# DRIVERS_CONNECTORS.net
KiCad netlist of a schematic drawn in Altium Designer
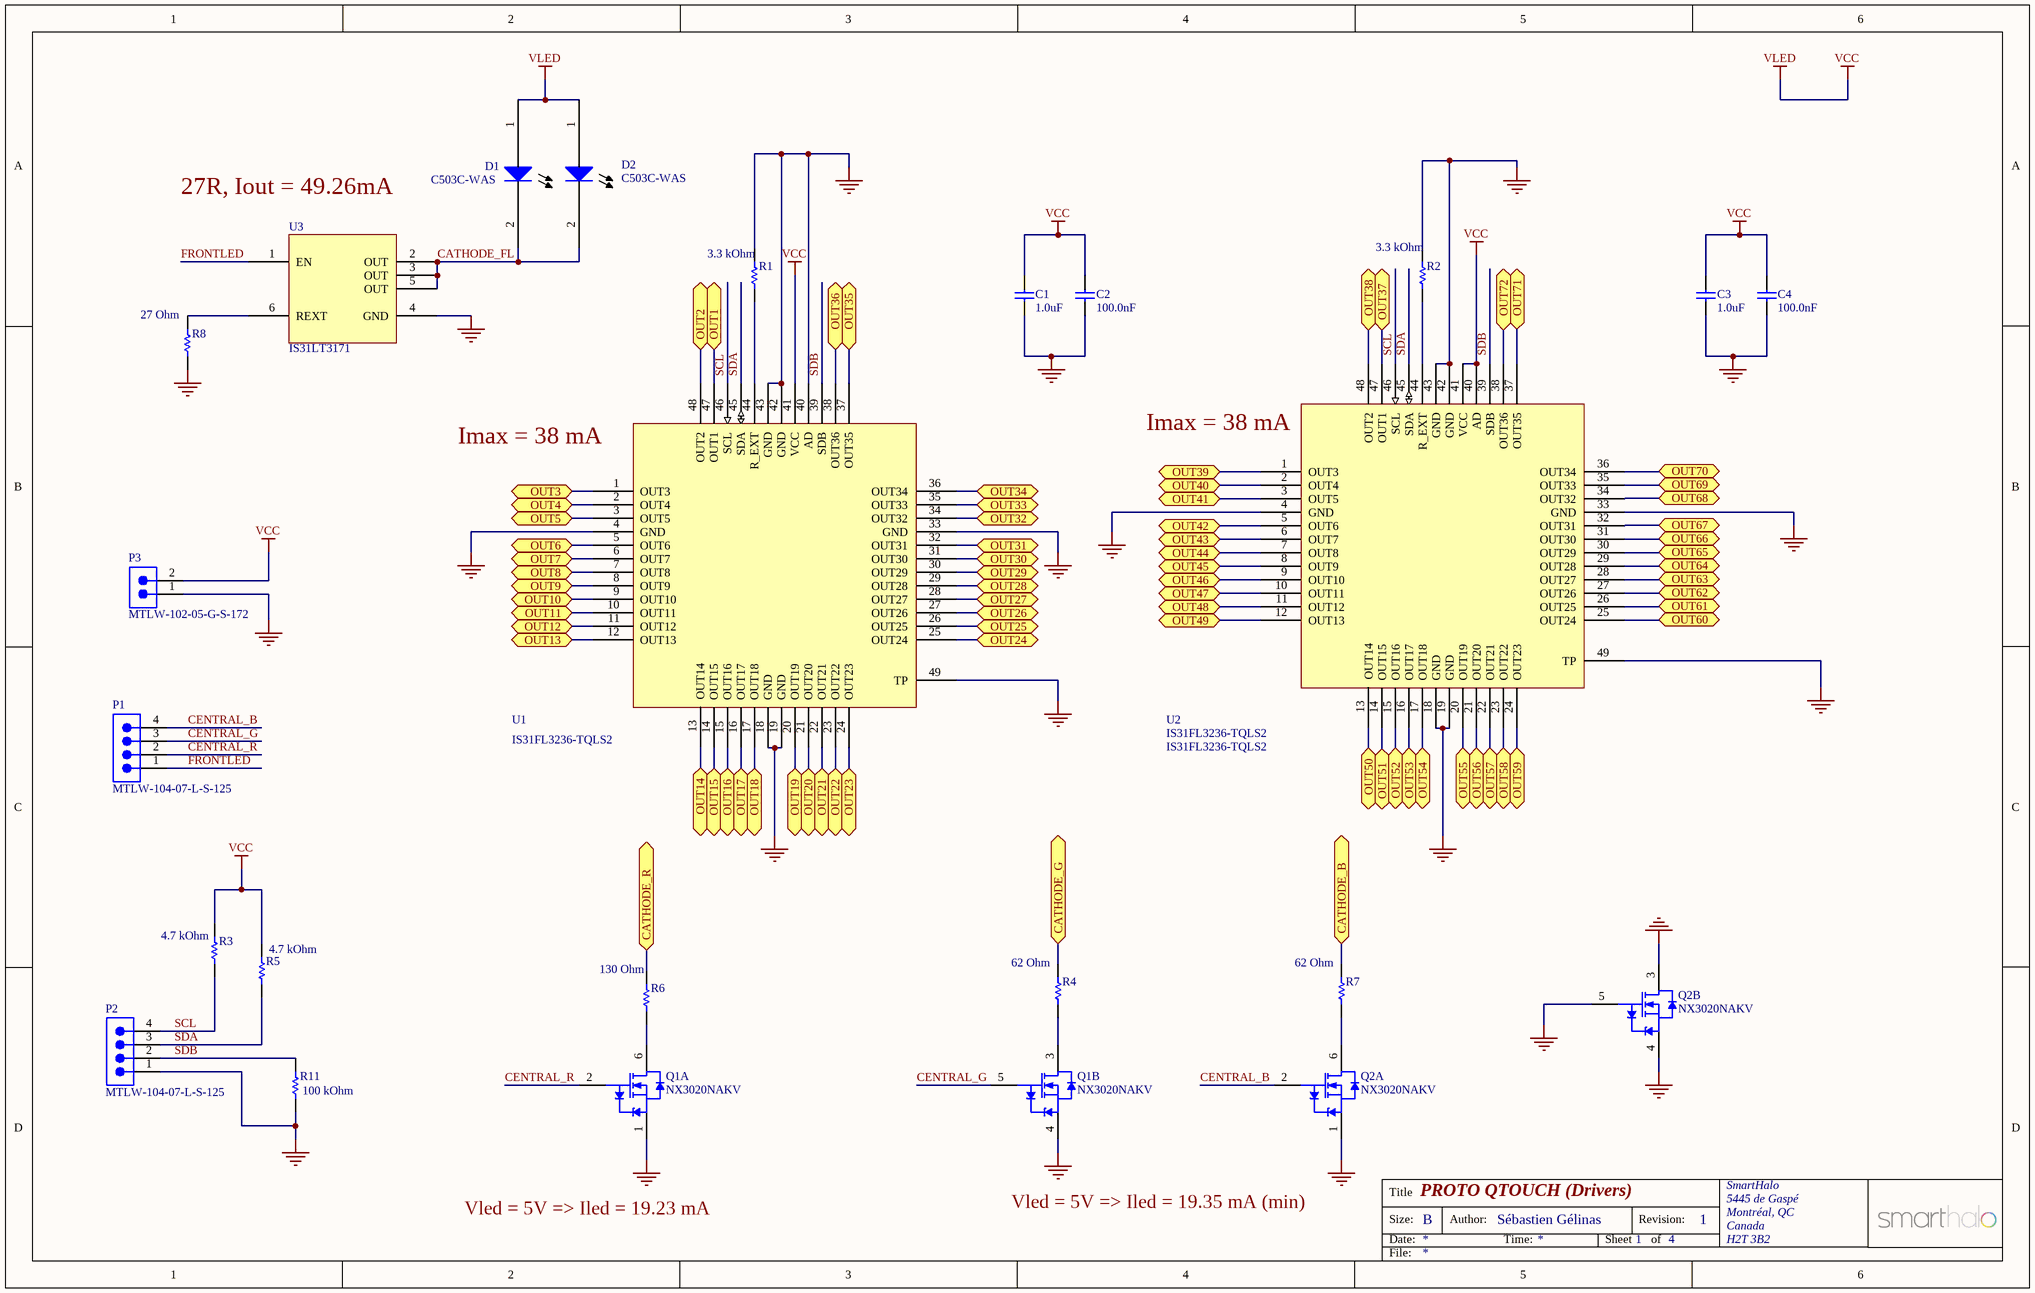
[diagram p0: DRIVERS_CONNECTORS.SchDoc]

(export (version "E")
  (design (tool "Eeschema 10.0.6"))
  (components
    (comp (ref "C1")
      (value "1.0uF")
      (footprint "CAPC0603(1608)100_N")
      (description "Chip Cap 0603 X7R 10%")
      (fields (field (name "PART NUMBER") "C0402-1n0") (field (name "PUBLISHER") "Nordic Semiconductor"))
      (libsource (lib "SmartHalo") (part "CAP0603"))
    )
    (comp (ref "C2")
      (value "100.0nF")
      (footprint "CAPC0603(1608)100_N")
      (description "Chip Cap 0603 X7R 10%")
      (fields (field (name "PART NUMBER") "C0402-1n0") (field (name "PUBLISHER") "Nordic Semiconductor"))
      (libsource (lib "SmartHalo") (part "CAP0603"))
    )
    (comp (ref "C3")
      (value "1.0uF")
      (footprint "CAPC0603(1608)100_N")
      (description "Chip Cap 0603 X7R 10%")
      (fields (field (name "PART NUMBER") "C0402-1n0") (field (name "PUBLISHER") "Nordic Semiconductor"))
      (libsource (lib "SmartHalo") (part "CAP0603"))
    )
    (comp (ref "C4")
      (value "100.0nF")
      (footprint "CAPC0603(1608)100_N")
      (description "Chip Cap 0603 X7R 10%")
      (fields (field (name "PART NUMBER") "C0402-1n0") (field (name "PUBLISHER") "Nordic Semiconductor"))
      (libsource (lib "SmartHalo") (part "CAP0603"))
    )
    (comp (ref "D1")
      (value "C503C-WAS")
      (footprint "FRONTLED_PADS")
      (description "Cree 5mm Round LED C503C-WAS")
      (libsource (lib "SmartHalo") (part "C503C-WAS"))
    )
    (comp (ref "D2")
      (value "C503C-WAS")
      (footprint "FRONTLED_PADS")
      (description "Cree 5mm Round LED C503C-WAS")
      (libsource (lib "SmartHalo") (part "C503C-WAS"))
    )
    (comp (ref "P1")
      (value "MTLW-104-07-L-S-125")
      (footprint "SMTC-MTLW-104-07-X-S-125")
      (fields (field (name "MANUFACTURER") "Samtec"))
      (libsource (lib "SmartHalo") (part "SMTC-MTLW-104-07-X-S-125"))
    )
    (comp (ref "P2")
      (value "MTLW-104-07-L-S-125")
      (footprint "SMTC-MTLW-104-07-X-S-125")
      (fields (field (name "MANUFACTURER") "Samtec"))
      (libsource (lib "SmartHalo") (part "SMTC-MTLW-104-07-X-S-125"))
    )
    (comp (ref "P3")
      (value "MTLW-102-05-G-S-172")
      (footprint "SMTC-MTLW-102-05-X-S-172")
      (fields (field (name "MANUFACTURER") "Samtec"))
      (libsource (lib "SmartHalo") (part "SMTC-MTLW-102-05-X-S-172"))
    )
    (comp (ref "Q1")
      (value "NX3020NAKV")
      (footprint "SOT666")
      (description "30 V, 200 mA dual N-channel Trench MOSFET")
      (fields (field (name "MANUFACTURER") "NXP Semiconductors"))
      (libsource (lib "SmartHalo") (part "NX3020NAKV"))
    )
    (comp (ref "Q2")
      (value "NX3020NAKV")
      (footprint "SOT666")
      (description "30 V, 200 mA dual N-channel Trench MOSFET")
      (fields (field (name "MANUFACTURER") "NXP Semiconductors"))
      (libsource (lib "SmartHalo") (part "NX3020NAKV"))
    )
    (comp (ref "R1")
      (value "3.3 kOhm")
      (footprint "RESC0603(1608)_M")
      (description "3K3 0.1W 5% 0603 (1608 Metric)  SMD")
      (fields (field (name "TOLERANCE") "5 %") (field (name "POWER") "0.1 W"))
      (libsource (lib "SmartHalo") (part "CMP-1012-00090-1"))
    )
    (comp (ref "R2")
      (value "3.3 kOhm")
      (footprint "RESC0603(1608)_M")
      (description "3K3 0.1W 5% 0603 (1608 Metric)  SMD")
      (fields (field (name "TOLERANCE") "5 %") (field (name "POWER") "0.1 W"))
      (libsource (lib "SmartHalo") (part "CMP-1012-00090-1"))
    )
    (comp (ref "R3")
      (value "4.7 kOhm")
      (footprint "RESC0603(1608)_M")
      (description "4K7 0.1W 5% 0603 (1608 Metric)  SMD")
      (fields (field (name "TOLERANCE") "5 %") (field (name "POWER") "0.1 W"))
      (libsource (lib "SmartHalo") (part "CMP-1012-00090-1"))
    )
    (comp (ref "R4")
      (value "62 Ohm")
      (footprint "RESC0603(1608)_M")
      (description "62R 0.1W 5% 0603 (1608 Metric)  SMD")
      (fields (field (name "TOLERANCE") "5 %") (field (name "POWER") "0.1 W"))
      (libsource (lib "SmartHalo") (part "CMP-1012-00090-1"))
    )
    (comp (ref "R5")
      (value "4.7 kOhm")
      (footprint "RESC0603(1608)_M")
      (description "4K7 0.1W 5% 0603 (1608 Metric)  SMD")
      (fields (field (name "TOLERANCE") "5 %") (field (name "POWER") "0.1 W"))
      (libsource (lib "SmartHalo") (part "CMP-1012-00090-1"))
    )
    (comp (ref "R6")
      (value "130 Ohm")
      (footprint "RESC0603(1608)_M")
      (description "130R 0.1W 5% 0603 (1608 Metric)  SMD")
      (fields (field (name "TOLERANCE") "5 %") (field (name "POWER") "0.1 W"))
      (libsource (lib "SmartHalo") (part "CMP-1012-00090-1"))
    )
    (comp (ref "R7")
      (value "62 Ohm")
      (footprint "RESC0603(1608)_M")
      (description "62R 0.1W 5% 0603 (1608 Metric)  SMD")
      (fields (field (name "TOLERANCE") "5 %") (field (name "POWER") "0.1 W"))
      (libsource (lib "SmartHalo") (part "CMP-1012-00090-1"))
    )
    (comp (ref "R8")
      (value "27 Ohm")
      (footprint "RESC0603(1608)_M")
      (description "27R 0.1W 5% 0603 (1608 Metric)  SMD")
      (fields (field (name "TOLERANCE") "5 %") (field (name "POWER") "0.1 W"))
      (libsource (lib "SmartHalo") (part "CMP-1012-00090-1"))
    )
    (comp (ref "R11")
      (value "100 kOhm")
      (footprint "RESC0603(1608)_M")
      (description "100k 0.1W 5% 0603 (1608 Metric)  SMD")
      (fields (field (name "TOLERANCE") "5 %") (field (name "POWER") "0.1 W"))
      (libsource (lib "SmartHalo") (part "CMP-1012-00090-1"))
    )
    (comp (ref "U1")
      (value "IS31FL3236-TQLS2")
      (footprint "TQFP48")
      (description "IC 36 CHANNELS LED DRIVER")
      (fields (field (name "MANUFACTURER") "ISSI"))
      (libsource (lib "SmartHalo") (part "IS31FL3236-TQLS2"))
    )
    (comp (ref "U2")
      (value "IS31FL3236-TQLS2")
      (footprint "TQFP48")
      (description "IC 36 CHANNELS LED DRIVER")
      (fields
        (field (name "MANUFACTURER") "ISSI")
        (field (name "MANUFACTURER PART NUMBER") "IS31FL3236-TQLS2")
      )
      (libsource (lib "SmartHalo") (part "IS31FL3236-TQLS2"))
    )
    (comp (ref "U3")
      (value "IS31LT3171")
      (footprint "SOT23-6")
      (description "10-TO-150MA CONSTANT-CURRENT LED DRIVER")
      (libsource (lib "SmartHalo") (part "IS31LT3171"))
    )
  )
  (nets
    (net (code "1") (name "/CATHODE_B") (class "Default")
      (node (ref "R7") (pin "2") (pinfunction "2_2") (pintype "passive"))
    )
    (net (code "2") (name "/CATHODE_FL") (class "Default")
      (node (ref "D1") (pin "2") (pinfunction "Cathode_2") (pintype "passive"))
      (node (ref "D2") (pin "2") (pinfunction "Cathode_2") (pintype "passive"))
      (node (ref "U3") (pin "2") (pinfunction "OUT_2") (pintype "passive"))
      (node (ref "U3") (pin "3") (pinfunction "OUT_3") (pintype "passive"))
      (node (ref "U3") (pin "5") (pinfunction "OUT_5") (pintype "passive"))
    )
    (net (code "3") (name "/CATHODE_G") (class "Default")
      (node (ref "R4") (pin "2") (pinfunction "2_2") (pintype "passive"))
    )
    (net (code "4") (name "/CATHODE_R") (class "Default")
      (node (ref "R6") (pin "2") (pinfunction "2_2") (pintype "passive"))
    )
    (net (code "5") (name "/CENTRAL_B") (class "Default")
      (node (ref "P1") (pin "4") (pinfunction "4_4") (pintype "passive"))
      (node (ref "Q2") (pin "2") (pinfunction "G1_2") (pintype "passive"))
    )
    (net (code "6") (name "/CENTRAL_G") (class "Default")
      (node (ref "P1") (pin "3") (pinfunction "3_3") (pintype "passive"))
      (node (ref "Q1") (pin "5") (pinfunction "G2_5") (pintype "passive"))
    )
    (net (code "7") (name "/CENTRAL_R") (class "Default")
      (node (ref "P1") (pin "2") (pinfunction "2_2") (pintype "passive"))
      (node (ref "Q1") (pin "2") (pinfunction "G1_2") (pintype "passive"))
    )
    (net (code "8") (name "/FRONTLED") (class "Default")
      (node (ref "P1") (pin "1") (pinfunction "1_1") (pintype "passive"))
      (node (ref "U3") (pin "1") (pinfunction "EN_1") (pintype "passive"))
    )
    (net (code "9") (name "/OUT1") (class "Default")
      (node (ref "U1") (pin "47") (pinfunction "OUT1_47") (pintype "passive"))
    )
    (net (code "10") (name "/OUT2") (class "Default")
      (node (ref "U1") (pin "48") (pinfunction "OUT2_48") (pintype "passive"))
    )
    (net (code "11") (name "/OUT3") (class "Default")
      (node (ref "U1") (pin "1") (pinfunction "OUT3_1") (pintype "passive"))
    )
    (net (code "12") (name "/OUT4") (class "Default")
      (node (ref "U1") (pin "2") (pinfunction "OUT4_2") (pintype "passive"))
    )
    (net (code "13") (name "/OUT5") (class "Default")
      (node (ref "U1") (pin "3") (pinfunction "OUT5_3") (pintype "passive"))
    )
    (net (code "14") (name "/OUT6") (class "Default")
      (node (ref "U1") (pin "5") (pinfunction "OUT6_5") (pintype "passive"))
    )
    (net (code "15") (name "/OUT7") (class "Default")
      (node (ref "U1") (pin "6") (pinfunction "OUT7_6") (pintype "passive"))
    )
    (net (code "16") (name "/OUT8") (class "Default")
      (node (ref "U1") (pin "7") (pinfunction "OUT8_7") (pintype "passive"))
    )
    (net (code "17") (name "/OUT9") (class "Default")
      (node (ref "U1") (pin "8") (pinfunction "OUT9_8") (pintype "passive"))
    )
    (net (code "18") (name "/OUT10") (class "Default")
      (node (ref "U1") (pin "9") (pinfunction "OUT10_9") (pintype "passive"))
    )
    (net (code "19") (name "/OUT11") (class "Default")
      (node (ref "U1") (pin "10") (pinfunction "OUT11_10") (pintype "passive"))
    )
    (net (code "20") (name "/OUT12") (class "Default")
      (node (ref "U1") (pin "11") (pinfunction "OUT12_11") (pintype "passive"))
    )
    (net (code "21") (name "/OUT13") (class "Default")
      (node (ref "U1") (pin "12") (pinfunction "OUT13_12") (pintype "passive"))
    )
    (net (code "22") (name "/OUT14") (class "Default")
      (node (ref "U1") (pin "13") (pinfunction "OUT14_13") (pintype "passive"))
    )
    (net (code "23") (name "/OUT15") (class "Default")
      (node (ref "U1") (pin "14") (pinfunction "OUT15_14") (pintype "passive"))
    )
    (net (code "24") (name "/OUT16") (class "Default")
      (node (ref "U1") (pin "15") (pinfunction "OUT16_15") (pintype "passive"))
    )
    (net (code "25") (name "/OUT17") (class "Default")
      (node (ref "U1") (pin "16") (pinfunction "OUT17_16") (pintype "passive"))
    )
    (net (code "26") (name "/OUT18") (class "Default")
      (node (ref "U1") (pin "17") (pinfunction "OUT18_17") (pintype "passive"))
    )
    (net (code "27") (name "/OUT19") (class "Default")
      (node (ref "U1") (pin "20") (pinfunction "OUT19_20") (pintype "passive"))
    )
    (net (code "28") (name "/OUT20") (class "Default")
      (node (ref "U1") (pin "21") (pinfunction "OUT20_21") (pintype "passive"))
    )
    (net (code "29") (name "/OUT21") (class "Default")
      (node (ref "U1") (pin "22") (pinfunction "OUT21_22") (pintype "passive"))
    )
    (net (code "30") (name "/OUT22") (class "Default")
      (node (ref "U1") (pin "23") (pinfunction "OUT22_23") (pintype "passive"))
    )
    (net (code "31") (name "/OUT23") (class "Default")
      (node (ref "U1") (pin "24") (pinfunction "OUT23_24") (pintype "passive"))
    )
    (net (code "32") (name "/OUT24") (class "Default")
      (node (ref "U1") (pin "25") (pinfunction "OUT24_25") (pintype "passive"))
    )
    (net (code "33") (name "/OUT25") (class "Default")
      (node (ref "U1") (pin "26") (pinfunction "OUT25_26") (pintype "passive"))
    )
    (net (code "34") (name "/OUT26") (class "Default")
      (node (ref "U1") (pin "27") (pinfunction "OUT26_27") (pintype "passive"))
    )
    (net (code "35") (name "/OUT27") (class "Default")
      (node (ref "U1") (pin "28") (pinfunction "OUT27_28") (pintype "passive"))
    )
    (net (code "36") (name "/OUT28") (class "Default")
      (node (ref "U1") (pin "29") (pinfunction "OUT28_29") (pintype "passive"))
    )
    (net (code "37") (name "/OUT29") (class "Default")
      (node (ref "U1") (pin "30") (pinfunction "OUT29_30") (pintype "passive"))
    )
    (net (code "38") (name "/OUT30") (class "Default")
      (node (ref "U1") (pin "31") (pinfunction "OUT30_31") (pintype "passive"))
    )
    (net (code "39") (name "/OUT31") (class "Default")
      (node (ref "U1") (pin "32") (pinfunction "OUT31_32") (pintype "passive"))
    )
    (net (code "40") (name "/OUT32") (class "Default")
      (node (ref "U1") (pin "34") (pinfunction "OUT32_34") (pintype "passive"))
    )
    (net (code "41") (name "/OUT33") (class "Default")
      (node (ref "U1") (pin "35") (pinfunction "OUT33_35") (pintype "passive"))
    )
    (net (code "42") (name "/OUT34") (class "Default")
      (node (ref "U1") (pin "36") (pinfunction "OUT34_36") (pintype "passive"))
    )
    (net (code "43") (name "/OUT35") (class "Default")
      (node (ref "U1") (pin "37") (pinfunction "OUT35_37") (pintype "passive"))
    )
    (net (code "44") (name "/OUT36") (class "Default")
      (node (ref "U1") (pin "38") (pinfunction "OUT36_38") (pintype "passive"))
    )
    (net (code "45") (name "/OUT37") (class "Default")
      (node (ref "U2") (pin "47") (pinfunction "OUT1_47") (pintype "passive"))
    )
    (net (code "46") (name "/OUT38") (class "Default")
      (node (ref "U2") (pin "48") (pinfunction "OUT2_48") (pintype "passive"))
    )
    (net (code "47") (name "/OUT39") (class "Default")
      (node (ref "U2") (pin "1") (pinfunction "OUT3_1") (pintype "passive"))
    )
    (net (code "48") (name "/OUT40") (class "Default")
      (node (ref "U2") (pin "2") (pinfunction "OUT4_2") (pintype "passive"))
    )
    (net (code "49") (name "/OUT41") (class "Default")
      (node (ref "U2") (pin "3") (pinfunction "OUT5_3") (pintype "passive"))
    )
    (net (code "50") (name "/OUT42") (class "Default")
      (node (ref "U2") (pin "5") (pinfunction "OUT6_5") (pintype "passive"))
    )
    (net (code "51") (name "/OUT43") (class "Default")
      (node (ref "U2") (pin "6") (pinfunction "OUT7_6") (pintype "passive"))
    )
    (net (code "52") (name "/OUT44") (class "Default")
      (node (ref "U2") (pin "7") (pinfunction "OUT8_7") (pintype "passive"))
    )
    (net (code "53") (name "/OUT45") (class "Default")
      (node (ref "U2") (pin "8") (pinfunction "OUT9_8") (pintype "passive"))
    )
    (net (code "54") (name "/OUT46") (class "Default")
      (node (ref "U2") (pin "9") (pinfunction "OUT10_9") (pintype "passive"))
    )
    (net (code "55") (name "/OUT47") (class "Default")
      (node (ref "U2") (pin "10") (pinfunction "OUT11_10") (pintype "passive"))
    )
    (net (code "56") (name "/OUT48") (class "Default")
      (node (ref "U2") (pin "11") (pinfunction "OUT12_11") (pintype "passive"))
    )
    (net (code "57") (name "/OUT49") (class "Default")
      (node (ref "U2") (pin "12") (pinfunction "OUT13_12") (pintype "passive"))
    )
    (net (code "58") (name "/OUT50") (class "Default")
      (node (ref "U2") (pin "13") (pinfunction "OUT14_13") (pintype "passive"))
    )
    (net (code "59") (name "/OUT51") (class "Default")
      (node (ref "U2") (pin "14") (pinfunction "OUT15_14") (pintype "passive"))
    )
    (net (code "60") (name "/OUT52") (class "Default")
      (node (ref "U2") (pin "15") (pinfunction "OUT16_15") (pintype "passive"))
    )
    (net (code "61") (name "/OUT53") (class "Default")
      (node (ref "U2") (pin "16") (pinfunction "OUT17_16") (pintype "passive"))
    )
    (net (code "62") (name "/OUT54") (class "Default")
      (node (ref "U2") (pin "17") (pinfunction "OUT18_17") (pintype "passive"))
    )
    (net (code "63") (name "/OUT55") (class "Default")
      (node (ref "U2") (pin "20") (pinfunction "OUT19_20") (pintype "passive"))
    )
    (net (code "64") (name "/OUT56") (class "Default")
      (node (ref "U2") (pin "21") (pinfunction "OUT20_21") (pintype "passive"))
    )
    (net (code "65") (name "/OUT57") (class "Default")
      (node (ref "U2") (pin "22") (pinfunction "OUT21_22") (pintype "passive"))
    )
    (net (code "66") (name "/OUT58") (class "Default")
      (node (ref "U2") (pin "23") (pinfunction "OUT22_23") (pintype "passive"))
    )
    (net (code "67") (name "/OUT59") (class "Default")
      (node (ref "U2") (pin "24") (pinfunction "OUT23_24") (pintype "passive"))
    )
    (net (code "68") (name "/OUT60") (class "Default")
      (node (ref "U2") (pin "25") (pinfunction "OUT24_25") (pintype "passive"))
    )
    (net (code "69") (name "/OUT61") (class "Default")
      (node (ref "U2") (pin "26") (pinfunction "OUT25_26") (pintype "passive"))
    )
    (net (code "70") (name "/OUT62") (class "Default")
      (node (ref "U2") (pin "27") (pinfunction "OUT26_27") (pintype "passive"))
    )
    (net (code "71") (name "/OUT63") (class "Default")
      (node (ref "U2") (pin "28") (pinfunction "OUT27_28") (pintype "passive"))
    )
    (net (code "72") (name "/OUT64") (class "Default")
      (node (ref "U2") (pin "29") (pinfunction "OUT28_29") (pintype "passive"))
    )
    (net (code "73") (name "/OUT65") (class "Default")
      (node (ref "U2") (pin "30") (pinfunction "OUT29_30") (pintype "passive"))
    )
    (net (code "74") (name "/OUT66") (class "Default")
      (node (ref "U2") (pin "31") (pinfunction "OUT30_31") (pintype "passive"))
    )
    (net (code "75") (name "/OUT67") (class "Default")
      (node (ref "U2") (pin "32") (pinfunction "OUT31_32") (pintype "passive"))
    )
    (net (code "76") (name "/OUT68") (class "Default")
      (node (ref "U2") (pin "34") (pinfunction "OUT32_34") (pintype "passive"))
    )
    (net (code "77") (name "/OUT69") (class "Default")
      (node (ref "U2") (pin "35") (pinfunction "OUT33_35") (pintype "passive"))
    )
    (net (code "78") (name "/OUT70") (class "Default")
      (node (ref "U2") (pin "36") (pinfunction "OUT34_36") (pintype "passive"))
    )
    (net (code "79") (name "/OUT71") (class "Default")
      (node (ref "U2") (pin "37") (pinfunction "OUT35_37") (pintype "passive"))
    )
    (net (code "80") (name "/OUT72") (class "Default")
      (node (ref "U2") (pin "38") (pinfunction "OUT36_38") (pintype "passive"))
    )
    (net (code "81") (name "/SCL") (class "Default")
      (node (ref "P2") (pin "4") (pinfunction "4_4") (pintype "passive"))
      (node (ref "R3") (pin "1") (pinfunction "1_1") (pintype "passive"))
      (node (ref "U1") (pin "46") (pinfunction "SCL_46") (pintype "input"))
      (node (ref "U2") (pin "46") (pinfunction "SCL_46") (pintype "input"))
    )
    (net (code "82") (name "/SDA") (class "Default")
      (node (ref "P2") (pin "3") (pinfunction "3_3") (pintype "passive"))
      (node (ref "R5") (pin "1") (pinfunction "1_1") (pintype "passive"))
      (node (ref "U1") (pin "45") (pinfunction "SDA_45") (pintype "bidirectional"))
      (node (ref "U2") (pin "45") (pinfunction "SDA_45") (pintype "bidirectional"))
    )
    (net (code "83") (name "/SDB") (class "Default")
      (node (ref "P2") (pin "2") (pinfunction "2_2") (pintype "passive"))
      (node (ref "R11") (pin "2") (pinfunction "2_2") (pintype "passive"))
      (node (ref "U1") (pin "39") (pinfunction "SDB_39") (pintype "passive"))
      (node (ref "U2") (pin "39") (pinfunction "SDB_39") (pintype "passive"))
    )
    (net (code "84") (name "GND") (class "Default")
      (node (ref "C1") (pin "2") (pinfunction "2_2") (pintype "passive"))
      (node (ref "C2") (pin "2") (pinfunction "2_2") (pintype "passive"))
      (node (ref "C3") (pin "2") (pinfunction "2_2") (pintype "passive"))
      (node (ref "C4") (pin "2") (pinfunction "2_2") (pintype "passive"))
      (node (ref "P2") (pin "1") (pinfunction "1_1") (pintype "passive"))
      (node (ref "P3") (pin "1") (pinfunction "1_1") (pintype "passive"))
      (node (ref "Q1") (pin "1") (pinfunction "S1_1") (pintype "passive"))
      (node (ref "Q1") (pin "4") (pinfunction "S2_4") (pintype "passive"))
      (node (ref "Q2") (pin "1") (pinfunction "S1_1") (pintype "passive"))
      (node (ref "Q2") (pin "3") (pinfunction "D2_3") (pintype "passive"))
      (node (ref "Q2") (pin "4") (pinfunction "S2_4") (pintype "passive"))
      (node (ref "Q2") (pin "5") (pinfunction "G2_5") (pintype "passive"))
      (node (ref "R1") (pin "2") (pinfunction "2_2") (pintype "passive"))
      (node (ref "R11") (pin "1") (pinfunction "1_1") (pintype "passive"))
      (node (ref "R2") (pin "2") (pinfunction "2_2") (pintype "passive"))
      (node (ref "R8") (pin "1") (pinfunction "1_1") (pintype "passive"))
      (node (ref "U1") (pin "18") (pinfunction "GND_18") (pintype "power_in"))
      (node (ref "U1") (pin "19") (pinfunction "GND_19") (pintype "power_in"))
      (node (ref "U1") (pin "33") (pinfunction "GND_33") (pintype "power_in"))
      (node (ref "U1") (pin "4") (pinfunction "GND_4") (pintype "power_in"))
      (node (ref "U1") (pin "40") (pinfunction "AD_40") (pintype "passive"))
      (node (ref "U1") (pin "42") (pinfunction "GND_42") (pintype "power_in"))
      (node (ref "U1") (pin "43") (pinfunction "GND_43") (pintype "power_in"))
      (node (ref "U1") (pin "49") (pinfunction "TP_49") (pintype "power_in"))
      (node (ref "U2") (pin "18") (pinfunction "GND_18") (pintype "power_in"))
      (node (ref "U2") (pin "19") (pinfunction "GND_19") (pintype "power_in"))
      (node (ref "U2") (pin "33") (pinfunction "GND_33") (pintype "power_in"))
      (node (ref "U2") (pin "4") (pinfunction "GND_4") (pintype "power_in"))
      (node (ref "U2") (pin "42") (pinfunction "GND_42") (pintype "power_in"))
      (node (ref "U2") (pin "43") (pinfunction "GND_43") (pintype "power_in"))
      (node (ref "U2") (pin "49") (pinfunction "TP_49") (pintype "power_in"))
      (node (ref "U3") (pin "4") (pinfunction "GND_4") (pintype "passive"))
    )
    (net (code "85") (name "Net-(Q1A-D1)") (class "Default")
      (node (ref "Q1") (pin "6") (pinfunction "D1_6") (pintype "passive"))
      (node (ref "R6") (pin "1") (pinfunction "1_1") (pintype "passive"))
    )
    (net (code "86") (name "Net-(Q1B-D2)") (class "Default")
      (node (ref "Q1") (pin "3") (pinfunction "D2_3") (pintype "passive"))
      (node (ref "R4") (pin "1") (pinfunction "1_1") (pintype "passive"))
    )
    (net (code "87") (name "Net-(Q2A-D1)") (class "Default")
      (node (ref "Q2") (pin "6") (pinfunction "D1_6") (pintype "passive"))
      (node (ref "R7") (pin "1") (pinfunction "1_1") (pintype "passive"))
    )
    (net (code "88") (name "Net-(U1-R_EXT)") (class "Default")
      (node (ref "R1") (pin "1") (pinfunction "1_1") (pintype "passive"))
      (node (ref "U1") (pin "44") (pinfunction "R_EXT_44") (pintype "passive"))
    )
    (net (code "89") (name "Net-(U2-R_EXT)") (class "Default")
      (node (ref "R2") (pin "1") (pinfunction "1_1") (pintype "passive"))
      (node (ref "U2") (pin "44") (pinfunction "R_EXT_44") (pintype "passive"))
    )
    (net (code "90") (name "Net-(U3-REXT)") (class "Default")
      (node (ref "R8") (pin "2") (pinfunction "2_2") (pintype "passive"))
      (node (ref "U3") (pin "6") (pinfunction "REXT_6") (pintype "passive"))
    )
    (net (code "91") (name "VCC") (class "Default")
      (node (ref "C1") (pin "1") (pinfunction "1_1") (pintype "passive"))
      (node (ref "C2") (pin "1") (pinfunction "1_1") (pintype "passive"))
      (node (ref "C3") (pin "1") (pinfunction "1_1") (pintype "passive"))
      (node (ref "C4") (pin "1") (pinfunction "1_1") (pintype "passive"))
      (node (ref "D1") (pin "1") (pinfunction "Anode_1") (pintype "passive"))
      (node (ref "D2") (pin "1") (pinfunction "Anode_1") (pintype "passive"))
      (node (ref "P3") (pin "2") (pinfunction "2_2") (pintype "passive"))
      (node (ref "R3") (pin "2") (pinfunction "2_2") (pintype "passive"))
      (node (ref "R5") (pin "2") (pinfunction "2_2") (pintype "passive"))
      (node (ref "U1") (pin "41") (pinfunction "VCC_41") (pintype "power_in"))
      (node (ref "U2") (pin "40") (pinfunction "AD_40") (pintype "passive"))
      (node (ref "U2") (pin "41") (pinfunction "VCC_41") (pintype "power_in"))
    )
  )
)
